# 1_STM32F103C8-core.net
KiCad netlist of a schematic drawn in Altium Designer
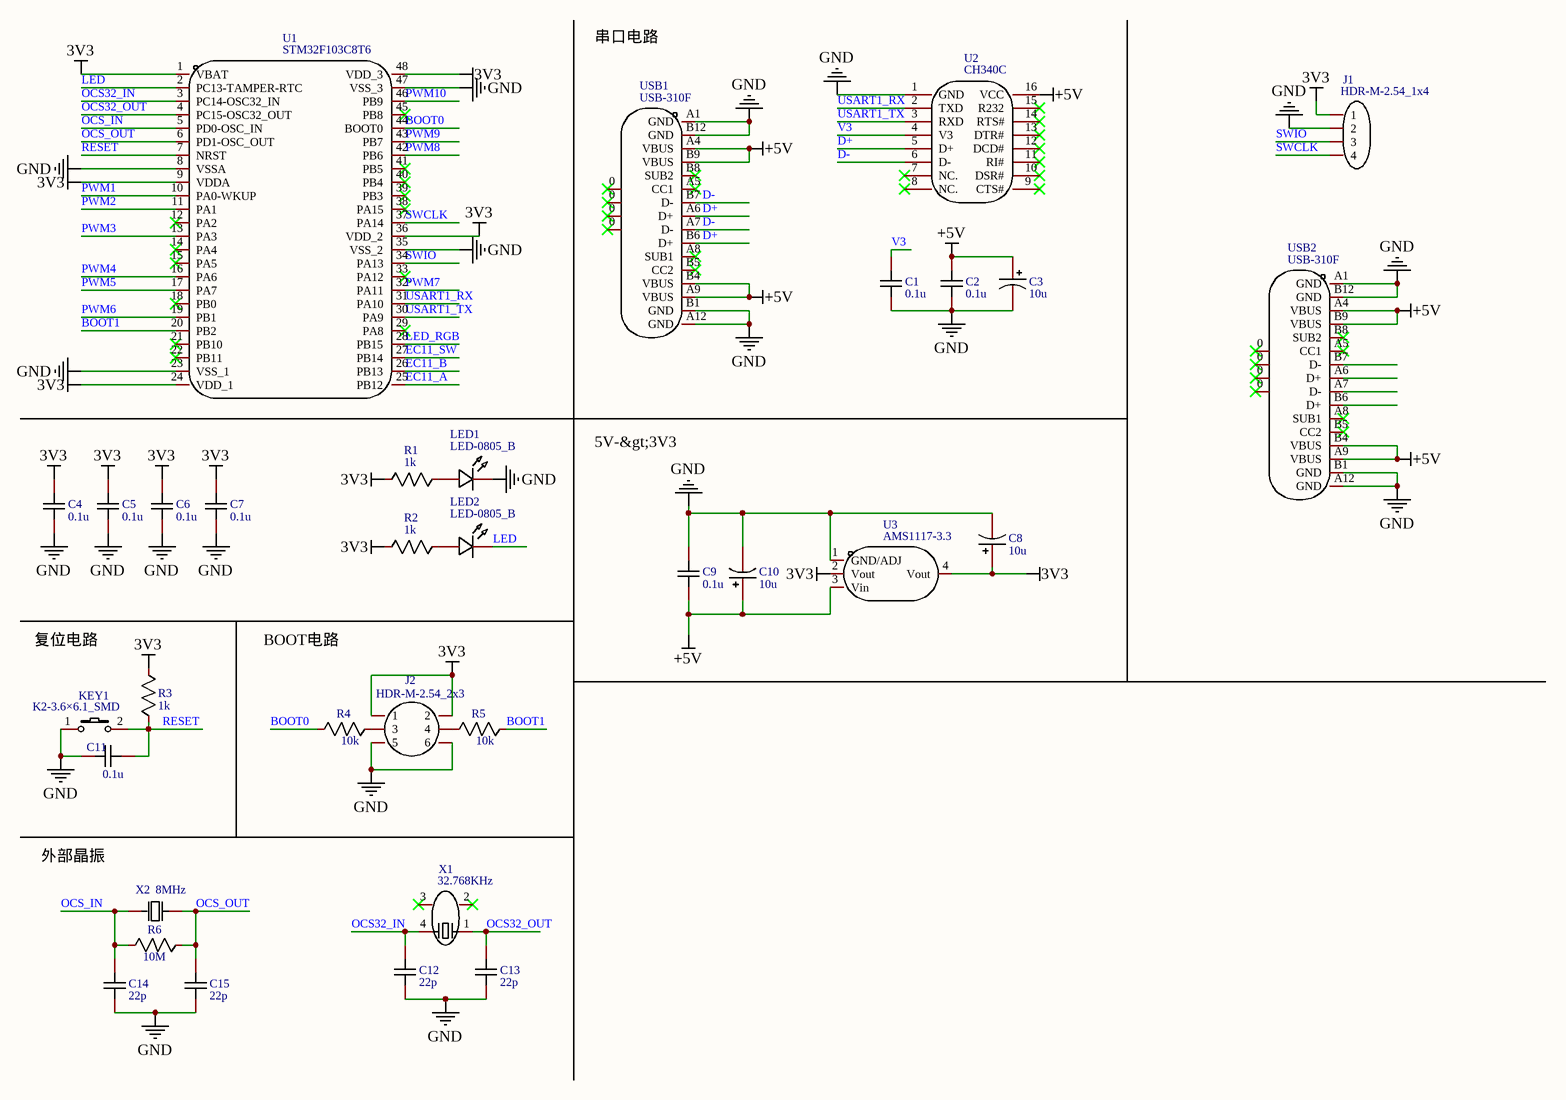
[diagram p0: 1_STM32F103C8-core.schdoc]

(export (version "E")
  (design (tool "Eeschema 10.0.6"))
  (components
    (comp (ref "C1")
      (value "0.1u")
      (footprint "C0805")
      (fields (field (name "NAME") "0.1u"))
      (libsource (lib "altium-import") (part "root_1_0.1u_"))
    )
    (comp (ref "C2")
      (value "0.1u")
      (footprint "C0805")
      (fields (field (name "NAME") "0.1u"))
      (libsource (lib "altium-import") (part "root_1_0.1u_"))
    )
    (comp (ref "C3")
      (value "10u")
      (footprint "CASE-A_3216")
      (fields (field (name "NAME") "10u"))
      (libsource (lib "altium-import") (part "root_3_10u_"))
    )
    (comp (ref "C4")
      (value "0.1u")
      (footprint "C0805")
      (fields (field (name "NAME") "0.1u"))
      (libsource (lib "altium-import") (part "root_1_0.1u_"))
    )
    (comp (ref "C5")
      (value "0.1u")
      (footprint "C0805")
      (fields (field (name "NAME") "0.1u"))
      (libsource (lib "altium-import") (part "root_1_0.1u_"))
    )
    (comp (ref "C6")
      (value "0.1u")
      (footprint "C0805")
      (fields (field (name "NAME") "0.1u"))
      (libsource (lib "altium-import") (part "root_1_0.1u_"))
    )
    (comp (ref "C7")
      (value "0.1u")
      (footprint "C0805")
      (fields (field (name "NAME") "0.1u"))
      (libsource (lib "altium-import") (part "root_1_0.1u_"))
    )
    (comp (ref "C8")
      (value "10u")
      (footprint "CASE-A_3216")
      (fields (field (name "NAME") "10u"))
      (libsource (lib "altium-import") (part "root_1_10u_"))
    )
    (comp (ref "C9")
      (value "0.1u")
      (footprint "C0805")
      (fields (field (name "NAME") "0.1u"))
      (libsource (lib "altium-import") (part "root_1_0.1u_"))
    )
    (comp (ref "C10")
      (value "10u")
      (footprint "CASE-A_3216")
      (fields (field (name "NAME") "10u"))
      (libsource (lib "altium-import") (part "root_1_10u_"))
    )
    (comp (ref "C11")
      (value "0.1u")
      (footprint "C0805")
      (fields (field (name "NAME") "0.1u"))
      (libsource (lib "altium-import") (part "root_2_0.1u_"))
    )
    (comp (ref "C12")
      (value "22p")
      (footprint "C0805")
      (fields (field (name "NAME") "22p"))
      (libsource (lib "altium-import") (part "root_1_22p_"))
    )
    (comp (ref "C13")
      (value "22p")
      (footprint "C0805")
      (fields (field (name "NAME") "22p"))
      (libsource (lib "altium-import") (part "root_1_22p_"))
    )
    (comp (ref "C14")
      (value "22p")
      (footprint "C0805")
      (fields (field (name "NAME") "22p"))
      (libsource (lib "altium-import") (part "root_1_22p_"))
    )
    (comp (ref "C15")
      (value "22p")
      (footprint "C0805")
      (fields (field (name "NAME") "22p"))
      (libsource (lib "altium-import") (part "root_1_22p_"))
    )
    (comp (ref "J1")
      (value "HDR-M-2.54_1x4")
      (footprint "HDR-M-2.54_1X4")
      (fields (field (name "NAME") "HDR-M-2.54_1x4"))
      (libsource (lib "altium-import") (part "root_0_HDR-M-2.54_1x4_"))
    )
    (comp (ref "J2")
      (value "HDR-M-2.54_2x3")
      (footprint "HDR-M-2.54_2X3")
      (fields (field (name "NAME") "HDR-M-2.54_2x3"))
      (libsource (lib "altium-import") (part "root_0_HDR-M-2.54_2x3_"))
    )
    (comp (ref "KEY1")
      (value "K2-3.6×6.1_SMD")
      (footprint "KEY-SMD_2P-L6.2-W3.6-LS8.0")
      (fields (field (name "NAME") "K2-3.6×6.1_SMD") (field (name "MANUFACTURER PART") "K2-1107ST-A4SW-06"))
      (libsource (lib "altium-import") (part "root_0_K2-1107ST-A4SW-06_"))
    )
    (comp (ref "LED1")
      (value "LED-0805_B")
      (footprint "LED0805_BLUE")
      (fields
        (field (name "NAME") "LED-0805_B")
        (field (name "MANUFACTURER") "方舟 ARKLED")
        (field (name "MANUFACTURER PART") "D-B080508B1-KS2")
      )
      (libsource (lib "altium-import") (part "root_0_D-B080508B1-KS2_"))
    )
    (comp (ref "LED2")
      (value "LED-0805_B")
      (footprint "LED0805_BLUE")
      (fields
        (field (name "NAME") "LED-0805_B")
        (field (name "MANUFACTURER") "方舟 ARKLED")
        (field (name "MANUFACTURER PART") "D-B080508B1-KS2")
      )
      (libsource (lib "altium-import") (part "root_0_D-B080508B1-KS2_"))
    )
    (comp (ref "R1")
      (value "1k")
      (footprint "R0805")
      (fields (field (name "NAME") "1k"))
      (libsource (lib "altium-import") (part "root_0_1k_"))
    )
    (comp (ref "R2")
      (value "1k")
      (footprint "R0805")
      (fields (field (name "NAME") "1k"))
      (libsource (lib "altium-import") (part "root_0_1k_"))
    )
    (comp (ref "R3")
      (value "1k")
      (footprint "R0805")
      (fields (field (name "NAME") "1k"))
      (libsource (lib "altium-import") (part "root_1_1k_"))
    )
    (comp (ref "R4")
      (value "10k")
      (footprint "R0805")
      (fields (field (name "NAME") "10k"))
      (libsource (lib "altium-import") (part "root_0_10k_"))
    )
    (comp (ref "R5")
      (value "10k")
      (footprint "R0805")
      (fields (field (name "NAME") "10k"))
      (libsource (lib "altium-import") (part "root_0_10k_"))
    )
    (comp (ref "R6")
      (value "10M")
      (footprint "R0805")
      (fields (field (name "NAME") "10M"))
      (libsource (lib "altium-import") (part "root_0_10M_"))
    )
    (comp (ref "U1")
      (value "STM32F103C8T6")
      (footprint "LQFP-48_L7.0-W7.0-P0.50-LS9.0-BL")
      (fields (field (name "NAME") "STM32F103C8T6") (field (name "MANUFACTURER") "STMicroelectronics"))
      (libsource (lib "altium-import") (part "root_0_STM32F103C8T6_"))
    )
    (comp (ref "U2")
      (value "CH340C")
      (footprint "SOP-16_L10.0-W3.9-P1.27-LS6.0-BL")
      (fields (field (name "NAME") "CH340C") (field (name "MANUFACTURER") "WCH"))
      (libsource (lib "altium-import") (part "root_0_CH340C_"))
    )
    (comp (ref "U3")
      (value "AMS1117-3.3")
      (footprint "SOT-223-3_L6.5-W3.4-P2.30-LS7.0-BR")
      (fields (field (name "NAME") "AMS1117-3.3") (field (name "MANUFACTURER") "AMS"))
      (libsource (lib "altium-import") (part "root_0_AMS1117-3.3_"))
    )
    (comp (ref "USB1")
      (value "USB-310F")
      (footprint "USB-C-SMD_20P-P0.50-L6.5-W8.9")
      (fields (field (name "NAME") "USB-310F") (field (name "MANUFACTURER") "HOOYA"))
      (libsource (lib "altium-import") (part "root_0_USB-310F_"))
    )
    (comp (ref "USB2")
      (value "USB-310F")
      (footprint "USB-C-SMD_20P-P0.50-L6.5-W8.9")
      (fields (field (name "NAME") "USB-310F") (field (name "MANUFACTURER") "HOOYA"))
      (libsource (lib "altium-import") (part "root_0_USB-310F_"))
    )
    (comp (ref "X1")
      (value "32.768KHz")
      (footprint "MC-306_4P-L8.0-W3.2-P5.5-BL")
      (fields
        (field (name "NAME") "32.768KHz")
        (field (name "MANUFACTURER PART") "Q13MC3061000300")
        (field (name "MANUFACTURER") "EPSON")
      )
      (libsource (lib "altium-import") (part "root_1_Q13MC3061000300_"))
    )
    (comp (ref "X2")
      (value "8MHz")
      (footprint "OSC-TH_L11.1-W4.7-P4.88")
      (description "频率:8MHz;频率公差:±20ppm;频率稳定度:±30ppm;负载电容:16pF;")
      (fields
        (field (name "NAME") "8MHz")
        (field (name "MANUFACTURER") "JYJE(晶友嘉)")
        (field (name "MANUFACTURER PART") "S1C80000VWGAC")
      )
      (libsource (lib "altium-import") (part "root_0_S1C80000VWGAC_"))
    )
  )
  (nets
    (net (code "1") (name "+5V") (class "Default")
      (node (ref "C10") (pin "1") (pinfunction "1_1") (pintype "passive"))
      (node (ref "C2") (pin "2") (pinfunction "2_2") (pintype "passive"))
      (node (ref "C3") (pin "1") (pinfunction "1_1") (pintype "passive"))
      (node (ref "C9") (pin "1") (pinfunction "1_1") (pintype "passive"))
      (node (ref "U2") (pin "16") (pinfunction "VCC_16") (pintype "passive"))
      (node (ref "U3") (pin "3") (pinfunction "Vin_3") (pintype "passive"))
      (node (ref "USB1") (pin "A4") (pinfunction "VBUS_A4") (pintype "passive"))
      (node (ref "USB1") (pin "A9") (pinfunction "VBUS_A9") (pintype "passive"))
      (node (ref "USB1") (pin "B4") (pinfunction "VBUS_B4") (pintype "passive"))
      (node (ref "USB1") (pin "B9") (pinfunction "VBUS_B9") (pintype "passive"))
      (node (ref "USB2") (pin "A4") (pinfunction "VBUS_A4") (pintype "passive"))
      (node (ref "USB2") (pin "A9") (pinfunction "VBUS_A9") (pintype "passive"))
      (node (ref "USB2") (pin "B4") (pinfunction "VBUS_B4") (pintype "passive"))
      (node (ref "USB2") (pin "B9") (pinfunction "VBUS_B9") (pintype "passive"))
    )
    (net (code "2") (name "/BOOT0") (class "Default")
      (node (ref "R4") (pin "1") (pinfunction "1_1") (pintype "passive"))
      (node (ref "U1") (pin "44") (pinfunction "BOOT0_44") (pintype "passive"))
    )
    (net (code "3") (name "/BOOT1") (class "Default")
      (node (ref "R5") (pin "2") (pinfunction "2_2") (pintype "passive"))
      (node (ref "U1") (pin "20") (pinfunction "PB2_20") (pintype "passive"))
    )
    (net (code "4") (name "/D+") (class "Default")
      (node (ref "U2") (pin "5") (pinfunction "D+_5") (pintype "passive"))
      (node (ref "USB1") (pin "A6") (pinfunction "D+_A6") (pintype "passive"))
      (node (ref "USB1") (pin "B6") (pinfunction "D+_B6") (pintype "passive"))
    )
    (net (code "5") (name "/D-") (class "Default")
      (node (ref "U2") (pin "6") (pinfunction "D-_6") (pintype "passive"))
      (node (ref "USB1") (pin "A7") (pinfunction "D-_A7") (pintype "passive"))
      (node (ref "USB1") (pin "B7") (pinfunction "D-_B7") (pintype "passive"))
    )
    (net (code "6") (name "/EC11_A") (class "Default")
      (node (ref "U1") (pin "25") (pinfunction "PB12_25") (pintype "passive"))
    )
    (net (code "7") (name "/EC11_B") (class "Default")
      (node (ref "U1") (pin "26") (pinfunction "PB13_26") (pintype "passive"))
    )
    (net (code "8") (name "/EC11_SW") (class "Default")
      (node (ref "U1") (pin "27") (pinfunction "PB14_27") (pintype "passive"))
    )
    (net (code "9") (name "/LED") (class "Default")
      (node (ref "LED2") (pin "2") (pinfunction "2_2") (pintype "passive"))
      (node (ref "U1") (pin "2") (pinfunction "PC13-TAMPER-RTC_2") (pintype "passive"))
    )
    (net (code "10") (name "/LED_RGB") (class "Default")
      (node (ref "U1") (pin "28") (pinfunction "PB15_28") (pintype "passive"))
    )
    (net (code "11") (name "/OCS32_IN") (class "Default")
      (node (ref "C12") (pin "2") (pinfunction "2_2") (pintype "passive"))
      (node (ref "U1") (pin "3") (pinfunction "PC14-OSC32_IN_3") (pintype "passive"))
      (node (ref "X1") (pin "4") (pinfunction "4_4") (pintype "passive"))
    )
    (net (code "12") (name "/OCS32_OUT") (class "Default")
      (node (ref "C13") (pin "2") (pinfunction "2_2") (pintype "passive"))
      (node (ref "U1") (pin "4") (pinfunction "PC15-OSC32_OUT_4") (pintype "passive"))
      (node (ref "X1") (pin "1") (pinfunction "1_1") (pintype "passive"))
    )
    (net (code "13") (name "/OCS_IN") (class "Default")
      (node (ref "C14") (pin "2") (pinfunction "2_2") (pintype "passive"))
      (node (ref "R6") (pin "1") (pinfunction "1_1") (pintype "passive"))
      (node (ref "U1") (pin "5") (pinfunction "PD0-OSC_IN_5") (pintype "passive"))
      (node (ref "X2") (pin "1") (pinfunction "OSC1_1") (pintype "passive"))
    )
    (net (code "14") (name "/OCS_OUT") (class "Default")
      (node (ref "C15") (pin "2") (pinfunction "2_2") (pintype "passive"))
      (node (ref "R6") (pin "2") (pinfunction "2_2") (pintype "passive"))
      (node (ref "U1") (pin "6") (pinfunction "PD1-OSC_OUT_6") (pintype "passive"))
      (node (ref "X2") (pin "2") (pinfunction "OSC2_2") (pintype "passive"))
    )
    (net (code "15") (name "/PWM1") (class "Default")
      (node (ref "U1") (pin "10") (pinfunction "PA0-WKUP_10") (pintype "passive"))
    )
    (net (code "16") (name "/PWM2") (class "Default")
      (node (ref "U1") (pin "11") (pinfunction "PA1_11") (pintype "passive"))
    )
    (net (code "17") (name "/PWM3") (class "Default")
      (node (ref "U1") (pin "13") (pinfunction "PA3_13") (pintype "passive"))
    )
    (net (code "18") (name "/PWM4") (class "Default")
      (node (ref "U1") (pin "16") (pinfunction "PA6_16") (pintype "passive"))
    )
    (net (code "19") (name "/PWM5") (class "Default")
      (node (ref "U1") (pin "17") (pinfunction "PA7_17") (pintype "passive"))
    )
    (net (code "20") (name "/PWM6") (class "Default")
      (node (ref "U1") (pin "19") (pinfunction "PB1_19") (pintype "passive"))
    )
    (net (code "21") (name "/PWM7") (class "Default")
      (node (ref "U1") (pin "32") (pinfunction "PA11_32") (pintype "passive"))
    )
    (net (code "22") (name "/PWM8") (class "Default")
      (node (ref "U1") (pin "42") (pinfunction "PB6_42") (pintype "passive"))
    )
    (net (code "23") (name "/PWM9") (class "Default")
      (node (ref "U1") (pin "43") (pinfunction "PB7_43") (pintype "passive"))
    )
    (net (code "24") (name "/PWM10") (class "Default")
      (node (ref "U1") (pin "46") (pinfunction "PB9_46") (pintype "passive"))
    )
    (net (code "25") (name "/RESET") (class "Default")
      (node (ref "C11") (pin "1") (pinfunction "1_1") (pintype "passive"))
      (node (ref "KEY1") (pin "2") (pinfunction "2_2") (pintype "passive"))
      (node (ref "R3") (pin "1") (pinfunction "1_1") (pintype "passive"))
      (node (ref "U1") (pin "7") (pinfunction "NRST_7") (pintype "passive"))
    )
    (net (code "26") (name "/SWCLK") (class "Default")
      (node (ref "J1") (pin "4") (pinfunction "4_4") (pintype "passive"))
      (node (ref "U1") (pin "37") (pinfunction "PA14_37") (pintype "passive"))
    )
    (net (code "27") (name "/SWIO") (class "Default")
      (node (ref "J1") (pin "3") (pinfunction "3_3") (pintype "passive"))
      (node (ref "U1") (pin "34") (pinfunction "PA13_34") (pintype "passive"))
    )
    (net (code "28") (name "/USART1_RX") (class "Default")
      (node (ref "U1") (pin "31") (pinfunction "PA10_31") (pintype "passive"))
      (node (ref "U2") (pin "2") (pinfunction "TXD_2") (pintype "passive"))
    )
    (net (code "29") (name "/USART1_TX") (class "Default")
      (node (ref "U1") (pin "30") (pinfunction "PA9_30") (pintype "passive"))
      (node (ref "U2") (pin "3") (pinfunction "RXD_3") (pintype "passive"))
    )
    (net (code "30") (name "/V3") (class "Default")
      (node (ref "C1") (pin "2") (pinfunction "2_2") (pintype "passive"))
      (node (ref "U2") (pin "4") (pinfunction "V3_4") (pintype "passive"))
    )
    (net (code "31") (name "3V3") (class "Default")
      (node (ref "C4") (pin "2") (pinfunction "2_2") (pintype "passive"))
      (node (ref "C5") (pin "2") (pinfunction "2_2") (pintype "passive"))
      (node (ref "C6") (pin "2") (pinfunction "2_2") (pintype "passive"))
      (node (ref "C7") (pin "2") (pinfunction "2_2") (pintype "passive"))
      (node (ref "C8") (pin "1") (pinfunction "1_1") (pintype "passive"))
      (node (ref "J1") (pin "1") (pinfunction "1_1") (pintype "passive"))
      (node (ref "J2") (pin "1") (pinfunction "1_1") (pintype "passive"))
      (node (ref "J2") (pin "2") (pinfunction "2_2") (pintype "passive"))
      (node (ref "R1") (pin "1") (pinfunction "1_1") (pintype "passive"))
      (node (ref "R2") (pin "1") (pinfunction "1_1") (pintype "passive"))
      (node (ref "R3") (pin "2") (pinfunction "2_2") (pintype "passive"))
      (node (ref "U1") (pin "1") (pinfunction "VBAT_1") (pintype "passive"))
      (node (ref "U1") (pin "24") (pinfunction "VDD_1_24") (pintype "passive"))
      (node (ref "U1") (pin "36") (pinfunction "VDD_2_36") (pintype "passive"))
      (node (ref "U1") (pin "48") (pinfunction "VDD_3_48") (pintype "passive"))
      (node (ref "U1") (pin "9") (pinfunction "VDDA_9") (pintype "passive"))
      (node (ref "U3") (pin "2") (pinfunction "Vout_2") (pintype "passive"))
      (node (ref "U3") (pin "4") (pinfunction "Vout_4") (pintype "passive"))
    )
    (net (code "32") (name "GND") (class "Default")
      (node (ref "C1") (pin "1") (pinfunction "1_1") (pintype "passive"))
      (node (ref "C10") (pin "2") (pinfunction "2_2") (pintype "passive"))
      (node (ref "C11") (pin "2") (pinfunction "2_2") (pintype "passive"))
      (node (ref "C12") (pin "1") (pinfunction "1_1") (pintype "passive"))
      (node (ref "C13") (pin "1") (pinfunction "1_1") (pintype "passive"))
      (node (ref "C14") (pin "1") (pinfunction "1_1") (pintype "passive"))
      (node (ref "C15") (pin "1") (pinfunction "1_1") (pintype "passive"))
      (node (ref "C2") (pin "1") (pinfunction "1_1") (pintype "passive"))
      (node (ref "C3") (pin "2") (pinfunction "2_2") (pintype "passive"))
      (node (ref "C4") (pin "1") (pinfunction "1_1") (pintype "passive"))
      (node (ref "C5") (pin "1") (pinfunction "1_1") (pintype "passive"))
      (node (ref "C6") (pin "1") (pinfunction "1_1") (pintype "passive"))
      (node (ref "C7") (pin "1") (pinfunction "1_1") (pintype "passive"))
      (node (ref "C8") (pin "2") (pinfunction "2_2") (pintype "passive"))
      (node (ref "C9") (pin "2") (pinfunction "2_2") (pintype "passive"))
      (node (ref "J1") (pin "2") (pinfunction "2_2") (pintype "passive"))
      (node (ref "J2") (pin "5") (pinfunction "5_5") (pintype "passive"))
      (node (ref "J2") (pin "6") (pinfunction "6_6") (pintype "passive"))
      (node (ref "KEY1") (pin "1") (pinfunction "1_1") (pintype "passive"))
      (node (ref "LED1") (pin "2") (pinfunction "2_2") (pintype "passive"))
      (node (ref "U1") (pin "23") (pinfunction "VSS_1_23") (pintype "passive"))
      (node (ref "U1") (pin "35") (pinfunction "VSS_2_35") (pintype "passive"))
      (node (ref "U1") (pin "47") (pinfunction "VSS_3_47") (pintype "passive"))
      (node (ref "U1") (pin "8") (pinfunction "VSSA_8") (pintype "passive"))
      (node (ref "U2") (pin "1") (pinfunction "GND_1") (pintype "passive"))
      (node (ref "U3") (pin "1") (pinfunction "GND/ADJ_1") (pintype "passive"))
      (node (ref "USB1") (pin "A1") (pinfunction "GND_A1") (pintype "passive"))
      (node (ref "USB1") (pin "A12") (pinfunction "GND_A12") (pintype "passive"))
      (node (ref "USB1") (pin "B1") (pinfunction "GND_B1") (pintype "passive"))
      (node (ref "USB1") (pin "B12") (pinfunction "GND_B12") (pintype "passive"))
      (node (ref "USB2") (pin "A1") (pinfunction "GND_A1") (pintype "passive"))
      (node (ref "USB2") (pin "A12") (pinfunction "GND_A12") (pintype "passive"))
      (node (ref "USB2") (pin "B1") (pinfunction "GND_B1") (pintype "passive"))
      (node (ref "USB2") (pin "B12") (pinfunction "GND_B12") (pintype "passive"))
    )
    (net (code "33") (name "Net-(J2-Pad3)") (class "Default")
      (node (ref "J2") (pin "3") (pinfunction "3_3") (pintype "passive"))
      (node (ref "R4") (pin "2") (pinfunction "2_2") (pintype "passive"))
    )
    (net (code "34") (name "Net-(J2-Pad4)") (class "Default")
      (node (ref "J2") (pin "4") (pinfunction "4_4") (pintype "passive"))
      (node (ref "R5") (pin "1") (pinfunction "1_1") (pintype "passive"))
    )
    (net (code "35") (name "Net-(LED1-Pad1)") (class "Default")
      (node (ref "LED1") (pin "1") (pinfunction "1_1") (pintype "passive"))
      (node (ref "R1") (pin "2") (pinfunction "2_2") (pintype "passive"))
    )
    (net (code "36") (name "Net-(LED2-Pad1)") (class "Default")
      (node (ref "LED2") (pin "1") (pinfunction "1_1") (pintype "passive"))
      (node (ref "R2") (pin "2") (pinfunction "2_2") (pintype "passive"))
    )
    (net (code "37") (name "unconnected-(U1-PA2-Pad12)") (class "Default")
      (node (ref "U1") (pin "12") (pinfunction "PA2_12") (pintype "passive+no_connect"))
    )
    (net (code "38") (name "unconnected-(U1-PA4-Pad14)") (class "Default")
      (node (ref "U1") (pin "14") (pinfunction "PA4_14") (pintype "passive+no_connect"))
    )
    (net (code "39") (name "unconnected-(U1-PA5-Pad15)") (class "Default")
      (node (ref "U1") (pin "15") (pinfunction "PA5_15") (pintype "passive+no_connect"))
    )
    (net (code "40") (name "unconnected-(U1-PA8-Pad29)") (class "Default")
      (node (ref "U1") (pin "29") (pinfunction "PA8_29") (pintype "passive+no_connect"))
    )
    (net (code "41") (name "unconnected-(U1-PA12-Pad33)") (class "Default")
      (node (ref "U1") (pin "33") (pinfunction "PA12_33") (pintype "passive+no_connect"))
    )
    (net (code "42") (name "unconnected-(U1-PA15-Pad38)") (class "Default")
      (node (ref "U1") (pin "38") (pinfunction "PA15_38") (pintype "passive+no_connect"))
    )
    (net (code "43") (name "unconnected-(U1-PB0-Pad18)") (class "Default")
      (node (ref "U1") (pin "18") (pinfunction "PB0_18") (pintype "passive+no_connect"))
    )
    (net (code "44") (name "unconnected-(U1-PB3-Pad39)") (class "Default")
      (node (ref "U1") (pin "39") (pinfunction "PB3_39") (pintype "passive+no_connect"))
    )
    (net (code "45") (name "unconnected-(U1-PB4-Pad40)") (class "Default")
      (node (ref "U1") (pin "40") (pinfunction "PB4_40") (pintype "passive+no_connect"))
    )
    (net (code "46") (name "unconnected-(U1-PB5-Pad41)") (class "Default")
      (node (ref "U1") (pin "41") (pinfunction "PB5_41") (pintype "passive+no_connect"))
    )
    (net (code "47") (name "unconnected-(U1-PB8-Pad45)") (class "Default")
      (node (ref "U1") (pin "45") (pinfunction "PB8_45") (pintype "passive+no_connect"))
    )
    (net (code "48") (name "unconnected-(U1-PB10-Pad21)") (class "Default")
      (node (ref "U1") (pin "21") (pinfunction "PB10_21") (pintype "passive+no_connect"))
    )
    (net (code "49") (name "unconnected-(U1-PB11-Pad22)") (class "Default")
      (node (ref "U1") (pin "22") (pinfunction "PB11_22") (pintype "passive+no_connect"))
    )
    (net (code "50") (name "unconnected-(U2-CTS#-Pad9)") (class "Default")
      (node (ref "U2") (pin "9") (pinfunction "CTS#_9") (pintype "passive+no_connect"))
    )
    (net (code "51") (name "unconnected-(U2-DCD#-Pad12)") (class "Default")
      (node (ref "U2") (pin "12") (pinfunction "DCD#_12") (pintype "passive+no_connect"))
    )
    (net (code "52") (name "unconnected-(U2-DSR#-Pad10)") (class "Default")
      (node (ref "U2") (pin "10") (pinfunction "DSR#_10") (pintype "passive+no_connect"))
    )
    (net (code "53") (name "unconnected-(U2-DTR#-Pad13)") (class "Default")
      (node (ref "U2") (pin "13") (pinfunction "DTR#_13") (pintype "passive+no_connect"))
    )
    (net (code "54") (name "unconnected-(U2-NC.-Pad7)") (class "Default")
      (node (ref "U2") (pin "7") (pinfunction "NC._7") (pintype "passive+no_connect"))
    )
    (net (code "55") (name "unconnected-(U2-NC.-Pad8)") (class "Default")
      (node (ref "U2") (pin "8") (pinfunction "NC._8") (pintype "passive+no_connect"))
    )
    (net (code "56") (name "unconnected-(U2-R232-Pad15)") (class "Default")
      (node (ref "U2") (pin "15") (pinfunction "R232_15") (pintype "passive+no_connect"))
    )
    (net (code "57") (name "unconnected-(U2-RI#-Pad11)") (class "Default")
      (node (ref "U2") (pin "11") (pinfunction "RI#_11") (pintype "passive+no_connect"))
    )
    (net (code "58") (name "unconnected-(U2-RTS#-Pad14)") (class "Default")
      (node (ref "U2") (pin "14") (pinfunction "RTS#_14") (pintype "passive+no_connect"))
    )
    (net (code "59") (name "unconnected-(USB1-CC1-PadA5)") (class "Default")
      (node (ref "USB1") (pin "A5") (pinfunction "CC1_A5") (pintype "passive+no_connect"))
    )
    (net (code "60") (name "unconnected-(USB1-CC2-PadB5)") (class "Default")
      (node (ref "USB1") (pin "B5") (pinfunction "CC2_B5") (pintype "passive+no_connect"))
    )
    (net (code "61") (name "unconnected-(USB1-Pad0)") (class "Default")
      (node (ref "USB1") (pin "0") (pinfunction "0_0") (pintype "passive+no_connect"))
    )
    (net (code "62") (name "unconnected-(USB1-Pad0)_1") (class "Default")
      (node (ref "USB1") (pin "0") (pinfunction "0_0") (pintype "passive+no_connect"))
    )
    (net (code "63") (name "unconnected-(USB1-Pad0)_2") (class "Default")
      (node (ref "USB1") (pin "0") (pinfunction "0_0") (pintype "passive+no_connect"))
    )
    (net (code "64") (name "unconnected-(USB1-Pad0)_3") (class "Default")
      (node (ref "USB1") (pin "0") (pinfunction "0_0") (pintype "passive+no_connect"))
    )
    (net (code "65") (name "unconnected-(USB1-SUB1-PadA8)") (class "Default")
      (node (ref "USB1") (pin "A8") (pinfunction "SUB1_A8") (pintype "passive+no_connect"))
    )
    (net (code "66") (name "unconnected-(USB1-SUB2-PadB8)") (class "Default")
      (node (ref "USB1") (pin "B8") (pinfunction "SUB2_B8") (pintype "passive+no_connect"))
    )
    (net (code "67") (name "unconnected-(USB2-CC1-PadA5)") (class "Default")
      (node (ref "USB2") (pin "A5") (pinfunction "CC1_A5") (pintype "passive+no_connect"))
    )
    (net (code "68") (name "unconnected-(USB2-CC2-PadB5)") (class "Default")
      (node (ref "USB2") (pin "B5") (pinfunction "CC2_B5") (pintype "passive+no_connect"))
    )
    (net (code "69") (name "unconnected-(USB2-D+-PadA6)") (class "Default")
      (node (ref "USB2") (pin "A6") (pinfunction "D+_A6") (pintype "passive"))
    )
    (net (code "70") (name "unconnected-(USB2-D+-PadB6)") (class "Default")
      (node (ref "USB2") (pin "B6") (pinfunction "D+_B6") (pintype "passive"))
    )
    (net (code "71") (name "unconnected-(USB2-D--PadA7)") (class "Default")
      (node (ref "USB2") (pin "A7") (pinfunction "D-_A7") (pintype "passive"))
    )
    (net (code "72") (name "unconnected-(USB2-D--PadB7)") (class "Default")
      (node (ref "USB2") (pin "B7") (pinfunction "D-_B7") (pintype "passive"))
    )
    (net (code "73") (name "unconnected-(USB2-Pad0)") (class "Default")
      (node (ref "USB2") (pin "0") (pinfunction "0_0") (pintype "passive+no_connect"))
    )
    (net (code "74") (name "unconnected-(USB2-Pad0)_1") (class "Default")
      (node (ref "USB2") (pin "0") (pinfunction "0_0") (pintype "passive+no_connect"))
    )
    (net (code "75") (name "unconnected-(USB2-Pad0)_2") (class "Default")
      (node (ref "USB2") (pin "0") (pinfunction "0_0") (pintype "passive+no_connect"))
    )
    (net (code "76") (name "unconnected-(USB2-Pad0)_3") (class "Default")
      (node (ref "USB2") (pin "0") (pinfunction "0_0") (pintype "passive+no_connect"))
    )
    (net (code "77") (name "unconnected-(USB2-SUB1-PadA8)") (class "Default")
      (node (ref "USB2") (pin "A8") (pinfunction "SUB1_A8") (pintype "passive+no_connect"))
    )
    (net (code "78") (name "unconnected-(USB2-SUB2-PadB8)") (class "Default")
      (node (ref "USB2") (pin "B8") (pinfunction "SUB2_B8") (pintype "passive+no_connect"))
    )
    (net (code "79") (name "unconnected-(X1-Pad2)") (class "Default")
      (node (ref "X1") (pin "2") (pinfunction "2_2") (pintype "passive+no_connect"))
    )
    (net (code "80") (name "unconnected-(X1-Pad3)") (class "Default")
      (node (ref "X1") (pin "3") (pinfunction "3_3") (pintype "passive+no_connect"))
    )
  )
)
